# CPLD.net
KiCad netlist of a schematic drawn in Altium Designer
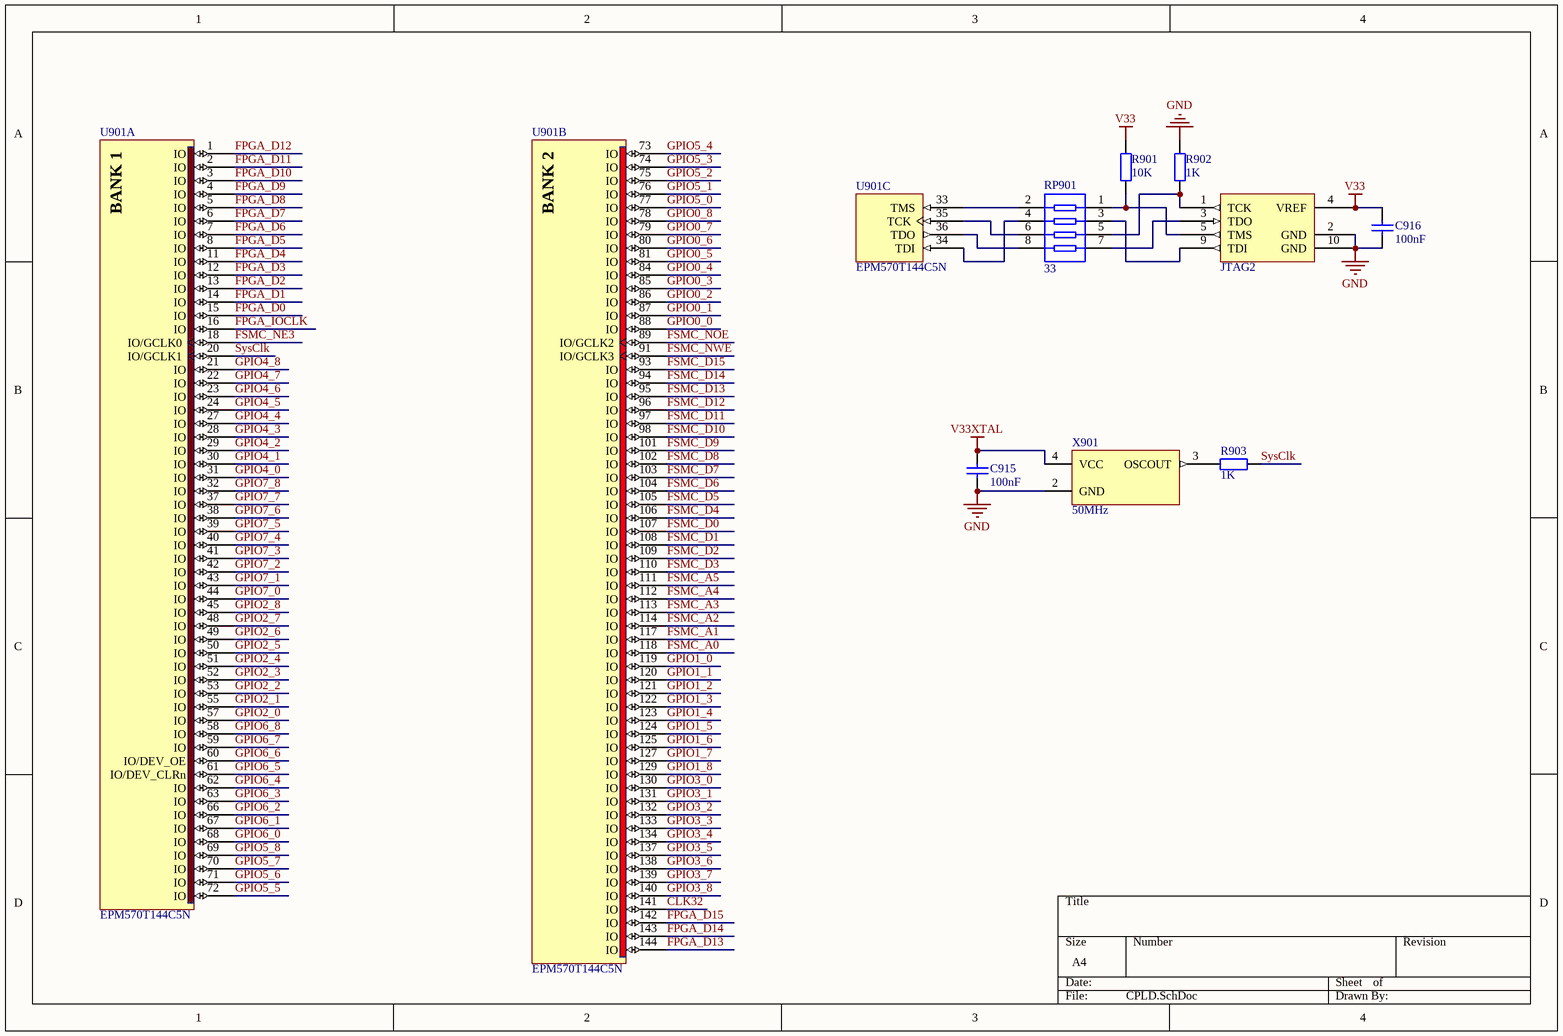
[diagram p0: CPLD.SchDoc]

(export (version "E")
  (design (tool "Eeschema 10.0.6"))
  (components
    (comp (ref "C915")
      (value "100nF")
      (footprint "0603C")
      (description "MLCC")
      (libsource (lib "Misc") (part "MLCC"))
    )
    (comp (ref "C916")
      (value "100nF")
      (footprint "0805C")
      (description "MLCC")
      (libsource (lib "Misc") (part "MLCC"))
    )
    (comp (ref "JTAG2")
      (value "JTAG_ALTERA")
      (footprint "JTAG10")
      (description "ALTERA JTAG port")
      (libsource (lib "JTAG") (part "JTAG_ALTERA"))
    )
    (comp (ref "R901")
      (value "10K")
      (footprint "0603R")
      (description "Resistor")
      (libsource (lib "Misc") (part "Resistor"))
    )
    (comp (ref "R902")
      (value "1K")
      (footprint "0603R")
      (description "Resistor")
      (libsource (lib "Misc") (part "Resistor"))
    )
    (comp (ref "R903")
      (value "1K")
      (footprint "0603R")
      (description "Resistor")
      (libsource (lib "") (part "Resistor_1"))
    )
    (comp (ref "RP901")
      (value "33")
      (footprint "8P4R_0603")
      (description "Isolated Resistor Network")
      (fields (field (name "Comment") "Res Pack"))
      (libsource (lib "Misc") (part "Res Pack"))
    )
    (comp (ref "U901")
      (value "EPM570T144C5N")
      (footprint "TQFP144_N")
      (libsource (lib "Altera MAX II") (part "EPM570T144C5N"))
    )
    (comp (ref "X901")
      (value "50MHz")
      (footprint "XTAL-7050")
      (description "Oscillator")
      (libsource (lib "XTAL") (part "Oscillator_50MHz"))
    )
  )
  (nets
    (net (code "1") (name "/CLK32") (class "Default")
      (node (ref "U901") (pin "141") (pinfunction "IO_141") (pintype "bidirectional"))
    )
    (net (code "2") (name "/FPGA_D0") (class "Default")
      (node (ref "U901") (pin "15") (pinfunction "IO_15") (pintype "bidirectional"))
    )
    (net (code "3") (name "/FPGA_D1") (class "Default")
      (node (ref "U901") (pin "14") (pinfunction "IO_14") (pintype "bidirectional"))
    )
    (net (code "4") (name "/FPGA_D2") (class "Default")
      (node (ref "U901") (pin "13") (pinfunction "IO_13") (pintype "bidirectional"))
    )
    (net (code "5") (name "/FPGA_D3") (class "Default")
      (node (ref "U901") (pin "12") (pinfunction "IO_12") (pintype "bidirectional"))
    )
    (net (code "6") (name "/FPGA_D4") (class "Default")
      (node (ref "U901") (pin "11") (pinfunction "IO_11") (pintype "bidirectional"))
    )
    (net (code "7") (name "/FPGA_D5") (class "Default")
      (node (ref "U901") (pin "8") (pinfunction "IO_8") (pintype "bidirectional"))
    )
    (net (code "8") (name "/FPGA_D6") (class "Default")
      (node (ref "U901") (pin "7") (pinfunction "IO_7") (pintype "bidirectional"))
    )
    (net (code "9") (name "/FPGA_D7") (class "Default")
      (node (ref "U901") (pin "6") (pinfunction "IO_6") (pintype "bidirectional"))
    )
    (net (code "10") (name "/FPGA_D8") (class "Default")
      (node (ref "U901") (pin "5") (pinfunction "IO_5") (pintype "bidirectional"))
    )
    (net (code "11") (name "/FPGA_D9") (class "Default")
      (node (ref "U901") (pin "4") (pinfunction "IO_4") (pintype "bidirectional"))
    )
    (net (code "12") (name "/FPGA_D10") (class "Default")
      (node (ref "U901") (pin "3") (pinfunction "IO_3") (pintype "bidirectional"))
    )
    (net (code "13") (name "/FPGA_D11") (class "Default")
      (node (ref "U901") (pin "2") (pinfunction "IO_2") (pintype "bidirectional"))
    )
    (net (code "14") (name "/FPGA_D12") (class "Default")
      (node (ref "U901") (pin "1") (pinfunction "IO_1") (pintype "bidirectional"))
    )
    (net (code "15") (name "/FPGA_D13") (class "Default")
      (node (ref "U901") (pin "144") (pinfunction "IO_144") (pintype "bidirectional"))
    )
    (net (code "16") (name "/FPGA_D14") (class "Default")
      (node (ref "U901") (pin "143") (pinfunction "IO_143") (pintype "bidirectional"))
    )
    (net (code "17") (name "/FPGA_D15") (class "Default")
      (node (ref "U901") (pin "142") (pinfunction "IO_142") (pintype "bidirectional"))
    )
    (net (code "18") (name "/FPGA_IOCLK") (class "Default")
      (node (ref "U901") (pin "16") (pinfunction "IO_16") (pintype "bidirectional"))
    )
    (net (code "19") (name "/FSMC_A0") (class "Default")
      (node (ref "U901") (pin "118") (pinfunction "IO_118") (pintype "bidirectional"))
    )
    (net (code "20") (name "/FSMC_A1") (class "Default")
      (node (ref "U901") (pin "117") (pinfunction "IO_117") (pintype "bidirectional"))
    )
    (net (code "21") (name "/FSMC_A2") (class "Default")
      (node (ref "U901") (pin "114") (pinfunction "IO_114") (pintype "bidirectional"))
    )
    (net (code "22") (name "/FSMC_A3") (class "Default")
      (node (ref "U901") (pin "113") (pinfunction "IO_113") (pintype "bidirectional"))
    )
    (net (code "23") (name "/FSMC_A4") (class "Default")
      (node (ref "U901") (pin "112") (pinfunction "IO_112") (pintype "bidirectional"))
    )
    (net (code "24") (name "/FSMC_A5") (class "Default")
      (node (ref "U901") (pin "111") (pinfunction "IO_111") (pintype "bidirectional"))
    )
    (net (code "25") (name "/FSMC_D0") (class "Default")
      (node (ref "U901") (pin "107") (pinfunction "IO_107") (pintype "bidirectional"))
    )
    (net (code "26") (name "/FSMC_D1") (class "Default")
      (node (ref "U901") (pin "108") (pinfunction "IO_108") (pintype "bidirectional"))
    )
    (net (code "27") (name "/FSMC_D2") (class "Default")
      (node (ref "U901") (pin "109") (pinfunction "IO_109") (pintype "bidirectional"))
    )
    (net (code "28") (name "/FSMC_D3") (class "Default")
      (node (ref "U901") (pin "110") (pinfunction "IO_110") (pintype "bidirectional"))
    )
    (net (code "29") (name "/FSMC_D4") (class "Default")
      (node (ref "U901") (pin "106") (pinfunction "IO_106") (pintype "bidirectional"))
    )
    (net (code "30") (name "/FSMC_D5") (class "Default")
      (node (ref "U901") (pin "105") (pinfunction "IO_105") (pintype "bidirectional"))
    )
    (net (code "31") (name "/FSMC_D6") (class "Default")
      (node (ref "U901") (pin "104") (pinfunction "IO_104") (pintype "bidirectional"))
    )
    (net (code "32") (name "/FSMC_D7") (class "Default")
      (node (ref "U901") (pin "103") (pinfunction "IO_103") (pintype "bidirectional"))
    )
    (net (code "33") (name "/FSMC_D8") (class "Default")
      (node (ref "U901") (pin "102") (pinfunction "IO_102") (pintype "bidirectional"))
    )
    (net (code "34") (name "/FSMC_D9") (class "Default")
      (node (ref "U901") (pin "101") (pinfunction "IO_101") (pintype "bidirectional"))
    )
    (net (code "35") (name "/FSMC_D10") (class "Default")
      (node (ref "U901") (pin "98") (pinfunction "IO_98") (pintype "bidirectional"))
    )
    (net (code "36") (name "/FSMC_D11") (class "Default")
      (node (ref "U901") (pin "97") (pinfunction "IO_97") (pintype "bidirectional"))
    )
    (net (code "37") (name "/FSMC_D12") (class "Default")
      (node (ref "U901") (pin "96") (pinfunction "IO_96") (pintype "bidirectional"))
    )
    (net (code "38") (name "/FSMC_D13") (class "Default")
      (node (ref "U901") (pin "95") (pinfunction "IO_95") (pintype "bidirectional"))
    )
    (net (code "39") (name "/FSMC_D14") (class "Default")
      (node (ref "U901") (pin "94") (pinfunction "IO_94") (pintype "bidirectional"))
    )
    (net (code "40") (name "/FSMC_D15") (class "Default")
      (node (ref "U901") (pin "93") (pinfunction "IO_93") (pintype "bidirectional"))
    )
    (net (code "41") (name "/FSMC_NE3") (class "Default")
      (node (ref "U901") (pin "18") (pinfunction "IO/GCLK0_18") (pintype "bidirectional"))
    )
    (net (code "42") (name "/FSMC_NOE") (class "Default")
      (node (ref "U901") (pin "89") (pinfunction "IO/GCLK2_89") (pintype "bidirectional"))
    )
    (net (code "43") (name "/FSMC_NWE") (class "Default")
      (node (ref "U901") (pin "91") (pinfunction "IO/GCLK3_91") (pintype "bidirectional"))
    )
    (net (code "44") (name "/GPIO0_0") (class "Default")
      (node (ref "U901") (pin "88") (pinfunction "IO_88") (pintype "bidirectional"))
    )
    (net (code "45") (name "/GPIO0_1") (class "Default")
      (node (ref "U901") (pin "87") (pinfunction "IO_87") (pintype "bidirectional"))
    )
    (net (code "46") (name "/GPIO0_2") (class "Default")
      (node (ref "U901") (pin "86") (pinfunction "IO_86") (pintype "bidirectional"))
    )
    (net (code "47") (name "/GPIO0_3") (class "Default")
      (node (ref "U901") (pin "85") (pinfunction "IO_85") (pintype "bidirectional"))
    )
    (net (code "48") (name "/GPIO0_4") (class "Default")
      (node (ref "U901") (pin "84") (pinfunction "IO_84") (pintype "bidirectional"))
    )
    (net (code "49") (name "/GPIO0_5") (class "Default")
      (node (ref "U901") (pin "81") (pinfunction "IO_81") (pintype "bidirectional"))
    )
    (net (code "50") (name "/GPIO0_6") (class "Default")
      (node (ref "U901") (pin "80") (pinfunction "IO_80") (pintype "bidirectional"))
    )
    (net (code "51") (name "/GPIO0_7") (class "Default")
      (node (ref "U901") (pin "79") (pinfunction "IO_79") (pintype "bidirectional"))
    )
    (net (code "52") (name "/GPIO0_8") (class "Default")
      (node (ref "U901") (pin "78") (pinfunction "IO_78") (pintype "bidirectional"))
    )
    (net (code "53") (name "/GPIO1_0") (class "Default")
      (node (ref "U901") (pin "119") (pinfunction "IO_119") (pintype "bidirectional"))
    )
    (net (code "54") (name "/GPIO1_1") (class "Default")
      (node (ref "U901") (pin "120") (pinfunction "IO_120") (pintype "bidirectional"))
    )
    (net (code "55") (name "/GPIO1_2") (class "Default")
      (node (ref "U901") (pin "121") (pinfunction "IO_121") (pintype "bidirectional"))
    )
    (net (code "56") (name "/GPIO1_3") (class "Default")
      (node (ref "U901") (pin "122") (pinfunction "IO_122") (pintype "bidirectional"))
    )
    (net (code "57") (name "/GPIO1_4") (class "Default")
      (node (ref "U901") (pin "123") (pinfunction "IO_123") (pintype "bidirectional"))
    )
    (net (code "58") (name "/GPIO1_5") (class "Default")
      (node (ref "U901") (pin "124") (pinfunction "IO_124") (pintype "bidirectional"))
    )
    (net (code "59") (name "/GPIO1_6") (class "Default")
      (node (ref "U901") (pin "125") (pinfunction "IO_125") (pintype "bidirectional"))
    )
    (net (code "60") (name "/GPIO1_7") (class "Default")
      (node (ref "U901") (pin "127") (pinfunction "IO_127") (pintype "bidirectional"))
    )
    (net (code "61") (name "/GPIO1_8") (class "Default")
      (node (ref "U901") (pin "129") (pinfunction "IO_129") (pintype "bidirectional"))
    )
    (net (code "62") (name "/GPIO2_0") (class "Default")
      (node (ref "U901") (pin "57") (pinfunction "IO_57") (pintype "bidirectional"))
    )
    (net (code "63") (name "/GPIO2_1") (class "Default")
      (node (ref "U901") (pin "55") (pinfunction "IO_55") (pintype "bidirectional"))
    )
    (net (code "64") (name "/GPIO2_2") (class "Default")
      (node (ref "U901") (pin "53") (pinfunction "IO_53") (pintype "bidirectional"))
    )
    (net (code "65") (name "/GPIO2_3") (class "Default")
      (node (ref "U901") (pin "52") (pinfunction "IO_52") (pintype "bidirectional"))
    )
    (net (code "66") (name "/GPIO2_4") (class "Default")
      (node (ref "U901") (pin "51") (pinfunction "IO_51") (pintype "bidirectional"))
    )
    (net (code "67") (name "/GPIO2_5") (class "Default")
      (node (ref "U901") (pin "50") (pinfunction "IO_50") (pintype "bidirectional"))
    )
    (net (code "68") (name "/GPIO2_6") (class "Default")
      (node (ref "U901") (pin "49") (pinfunction "IO_49") (pintype "bidirectional"))
    )
    (net (code "69") (name "/GPIO2_7") (class "Default")
      (node (ref "U901") (pin "48") (pinfunction "IO_48") (pintype "bidirectional"))
    )
    (net (code "70") (name "/GPIO2_8") (class "Default")
      (node (ref "U901") (pin "45") (pinfunction "IO_45") (pintype "bidirectional"))
    )
    (net (code "71") (name "/GPIO3_0") (class "Default")
      (node (ref "U901") (pin "130") (pinfunction "IO_130") (pintype "bidirectional"))
    )
    (net (code "72") (name "/GPIO3_1") (class "Default")
      (node (ref "U901") (pin "131") (pinfunction "IO_131") (pintype "bidirectional"))
    )
    (net (code "73") (name "/GPIO3_2") (class "Default")
      (node (ref "U901") (pin "132") (pinfunction "IO_132") (pintype "bidirectional"))
    )
    (net (code "74") (name "/GPIO3_3") (class "Default")
      (node (ref "U901") (pin "133") (pinfunction "IO_133") (pintype "bidirectional"))
    )
    (net (code "75") (name "/GPIO3_4") (class "Default")
      (node (ref "U901") (pin "134") (pinfunction "IO_134") (pintype "bidirectional"))
    )
    (net (code "76") (name "/GPIO3_5") (class "Default")
      (node (ref "U901") (pin "137") (pinfunction "IO_137") (pintype "bidirectional"))
    )
    (net (code "77") (name "/GPIO3_6") (class "Default")
      (node (ref "U901") (pin "138") (pinfunction "IO_138") (pintype "bidirectional"))
    )
    (net (code "78") (name "/GPIO3_7") (class "Default")
      (node (ref "U901") (pin "139") (pinfunction "IO_139") (pintype "bidirectional"))
    )
    (net (code "79") (name "/GPIO3_8") (class "Default")
      (node (ref "U901") (pin "140") (pinfunction "IO_140") (pintype "bidirectional"))
    )
    (net (code "80") (name "/GPIO4_0") (class "Default")
      (node (ref "U901") (pin "31") (pinfunction "IO_31") (pintype "bidirectional"))
    )
    (net (code "81") (name "/GPIO4_1") (class "Default")
      (node (ref "U901") (pin "30") (pinfunction "IO_30") (pintype "bidirectional"))
    )
    (net (code "82") (name "/GPIO4_2") (class "Default")
      (node (ref "U901") (pin "29") (pinfunction "IO_29") (pintype "bidirectional"))
    )
    (net (code "83") (name "/GPIO4_3") (class "Default")
      (node (ref "U901") (pin "28") (pinfunction "IO_28") (pintype "bidirectional"))
    )
    (net (code "84") (name "/GPIO4_4") (class "Default")
      (node (ref "U901") (pin "27") (pinfunction "IO_27") (pintype "bidirectional"))
    )
    (net (code "85") (name "/GPIO4_5") (class "Default")
      (node (ref "U901") (pin "24") (pinfunction "IO_24") (pintype "bidirectional"))
    )
    (net (code "86") (name "/GPIO4_6") (class "Default")
      (node (ref "U901") (pin "23") (pinfunction "IO_23") (pintype "bidirectional"))
    )
    (net (code "87") (name "/GPIO4_7") (class "Default")
      (node (ref "U901") (pin "22") (pinfunction "IO_22") (pintype "bidirectional"))
    )
    (net (code "88") (name "/GPIO4_8") (class "Default")
      (node (ref "U901") (pin "21") (pinfunction "IO_21") (pintype "bidirectional"))
    )
    (net (code "89") (name "/GPIO5_0") (class "Default")
      (node (ref "U901") (pin "77") (pinfunction "IO_77") (pintype "bidirectional"))
    )
    (net (code "90") (name "/GPIO5_1") (class "Default")
      (node (ref "U901") (pin "76") (pinfunction "IO_76") (pintype "bidirectional"))
    )
    (net (code "91") (name "/GPIO5_2") (class "Default")
      (node (ref "U901") (pin "75") (pinfunction "IO_75") (pintype "bidirectional"))
    )
    (net (code "92") (name "/GPIO5_3") (class "Default")
      (node (ref "U901") (pin "74") (pinfunction "IO_74") (pintype "bidirectional"))
    )
    (net (code "93") (name "/GPIO5_4") (class "Default")
      (node (ref "U901") (pin "73") (pinfunction "IO_73") (pintype "bidirectional"))
    )
    (net (code "94") (name "/GPIO5_5") (class "Default")
      (node (ref "U901") (pin "72") (pinfunction "IO_72") (pintype "bidirectional"))
    )
    (net (code "95") (name "/GPIO5_6") (class "Default")
      (node (ref "U901") (pin "71") (pinfunction "IO_71") (pintype "bidirectional"))
    )
    (net (code "96") (name "/GPIO5_7") (class "Default")
      (node (ref "U901") (pin "70") (pinfunction "IO_70") (pintype "bidirectional"))
    )
    (net (code "97") (name "/GPIO5_8") (class "Default")
      (node (ref "U901") (pin "69") (pinfunction "IO_69") (pintype "bidirectional"))
    )
    (net (code "98") (name "/GPIO6_0") (class "Default")
      (node (ref "U901") (pin "68") (pinfunction "IO_68") (pintype "bidirectional"))
    )
    (net (code "99") (name "/GPIO6_1") (class "Default")
      (node (ref "U901") (pin "67") (pinfunction "IO_67") (pintype "bidirectional"))
    )
    (net (code "100") (name "/GPIO6_2") (class "Default")
      (node (ref "U901") (pin "66") (pinfunction "IO_66") (pintype "bidirectional"))
    )
    (net (code "101") (name "/GPIO6_3") (class "Default")
      (node (ref "U901") (pin "63") (pinfunction "IO_63") (pintype "bidirectional"))
    )
    (net (code "102") (name "/GPIO6_4") (class "Default")
      (node (ref "U901") (pin "62") (pinfunction "IO_62") (pintype "bidirectional"))
    )
    (net (code "103") (name "/GPIO6_5") (class "Default")
      (node (ref "U901") (pin "61") (pinfunction "IO/DEV_CLRn_61") (pintype "bidirectional"))
    )
    (net (code "104") (name "/GPIO6_6") (class "Default")
      (node (ref "U901") (pin "60") (pinfunction "IO/DEV_OE_60") (pintype "bidirectional"))
    )
    (net (code "105") (name "/GPIO6_7") (class "Default")
      (node (ref "U901") (pin "59") (pinfunction "IO_59") (pintype "bidirectional"))
    )
    (net (code "106") (name "/GPIO6_8") (class "Default")
      (node (ref "U901") (pin "58") (pinfunction "IO_58") (pintype "bidirectional"))
    )
    (net (code "107") (name "/GPIO7_0") (class "Default")
      (node (ref "U901") (pin "44") (pinfunction "IO_44") (pintype "bidirectional"))
    )
    (net (code "108") (name "/GPIO7_1") (class "Default")
      (node (ref "U901") (pin "43") (pinfunction "IO_43") (pintype "bidirectional"))
    )
    (net (code "109") (name "/GPIO7_2") (class "Default")
      (node (ref "U901") (pin "42") (pinfunction "IO_42") (pintype "bidirectional"))
    )
    (net (code "110") (name "/GPIO7_3") (class "Default")
      (node (ref "U901") (pin "41") (pinfunction "IO_41") (pintype "bidirectional"))
    )
    (net (code "111") (name "/GPIO7_4") (class "Default")
      (node (ref "U901") (pin "40") (pinfunction "IO_40") (pintype "bidirectional"))
    )
    (net (code "112") (name "/GPIO7_5") (class "Default")
      (node (ref "U901") (pin "39") (pinfunction "IO_39") (pintype "bidirectional"))
    )
    (net (code "113") (name "/GPIO7_6") (class "Default")
      (node (ref "U901") (pin "38") (pinfunction "IO_38") (pintype "bidirectional"))
    )
    (net (code "114") (name "/GPIO7_7") (class "Default")
      (node (ref "U901") (pin "37") (pinfunction "IO_37") (pintype "bidirectional"))
    )
    (net (code "115") (name "/GPIO7_8") (class "Default")
      (node (ref "U901") (pin "32") (pinfunction "IO_32") (pintype "bidirectional"))
    )
    (net (code "116") (name "/SysClk") (class "Default")
      (node (ref "R903") (pin "2") (pinfunction "2_2") (pintype "passive"))
      (node (ref "U901") (pin "20") (pinfunction "IO/GCLK1_20") (pintype "bidirectional"))
    )
    (net (code "117") (name "GND") (class "Default")
      (node (ref "C915") (pin "1") (pinfunction "1_1") (pintype "passive"))
      (node (ref "C916") (pin "1") (pinfunction "1_1") (pintype "passive"))
      (node (ref "JTAG2") (pin "10") (pinfunction "GND_10") (pintype "power_in"))
      (node (ref "JTAG2") (pin "2") (pinfunction "GND_2") (pintype "power_in"))
      (node (ref "R902") (pin "2") (pinfunction "2_2") (pintype "passive"))
      (node (ref "X901") (pin "2") (pinfunction "GND_2") (pintype "power_in"))
    )
    (net (code "118") (name "Net-(JTAG2-TCK)") (class "Default")
      (node (ref "JTAG2") (pin "1") (pinfunction "TCK_1") (pintype "output"))
      (node (ref "R902") (pin "1") (pinfunction "1_1") (pintype "passive"))
      (node (ref "RP901") (pin "5") (pinfunction "5_5") (pintype "passive"))
    )
    (net (code "119") (name "Net-(JTAG2-TDI)") (class "Default")
      (node (ref "JTAG2") (pin "9") (pinfunction "TDI_9") (pintype "output"))
      (node (ref "RP901") (pin "3") (pinfunction "3_3") (pintype "passive"))
    )
    (net (code "120") (name "Net-(JTAG2-TDO)") (class "Default")
      (node (ref "JTAG2") (pin "3") (pinfunction "TDO_3") (pintype "input"))
      (node (ref "RP901") (pin "7") (pinfunction "7_7") (pintype "passive"))
    )
    (net (code "121") (name "Net-(JTAG2-TMS)") (class "Default")
      (node (ref "JTAG2") (pin "5") (pinfunction "TMS_5") (pintype "output"))
      (node (ref "R901") (pin "1") (pinfunction "1_1") (pintype "passive"))
      (node (ref "RP901") (pin "1") (pinfunction "1_1") (pintype "passive"))
    )
    (net (code "122") (name "Net-(U901C-TCK)") (class "Default")
      (node (ref "RP901") (pin "6") (pinfunction "6_6") (pintype "passive"))
      (node (ref "U901") (pin "35") (pinfunction "TCK_35") (pintype "input"))
    )
    (net (code "123") (name "Net-(U901C-TDI)") (class "Default")
      (node (ref "RP901") (pin "4") (pinfunction "4_4") (pintype "passive"))
      (node (ref "U901") (pin "34") (pinfunction "TDI_34") (pintype "input"))
    )
    (net (code "124") (name "Net-(U901C-TDO)") (class "Default")
      (node (ref "RP901") (pin "8") (pinfunction "8_8") (pintype "passive"))
      (node (ref "U901") (pin "36") (pinfunction "TDO_36") (pintype "output"))
    )
    (net (code "125") (name "Net-(U901C-TMS)") (class "Default")
      (node (ref "RP901") (pin "2") (pinfunction "2_2") (pintype "passive"))
      (node (ref "U901") (pin "33") (pinfunction "TMS_33") (pintype "input"))
    )
    (net (code "126") (name "Net-(X901-OSCOUT)") (class "Default")
      (node (ref "R903") (pin "1") (pinfunction "1_1") (pintype "passive"))
      (node (ref "X901") (pin "3") (pinfunction "OSCOUT_3") (pintype "output"))
    )
    (net (code "127") (name "V33") (class "Default")
      (node (ref "C916") (pin "2") (pinfunction "2_2") (pintype "passive"))
      (node (ref "JTAG2") (pin "4") (pinfunction "VREF_4") (pintype "power_in"))
      (node (ref "R901") (pin "2") (pinfunction "2_2") (pintype "passive"))
    )
    (net (code "128") (name "V33XTAL") (class "Default")
      (node (ref "C915") (pin "2") (pinfunction "2_2") (pintype "passive"))
      (node (ref "X901") (pin "4") (pinfunction "VCC_4") (pintype "power_in"))
    )
  )
)
